# Audio.net
KiCad netlist of a schematic drawn in Altium Designer
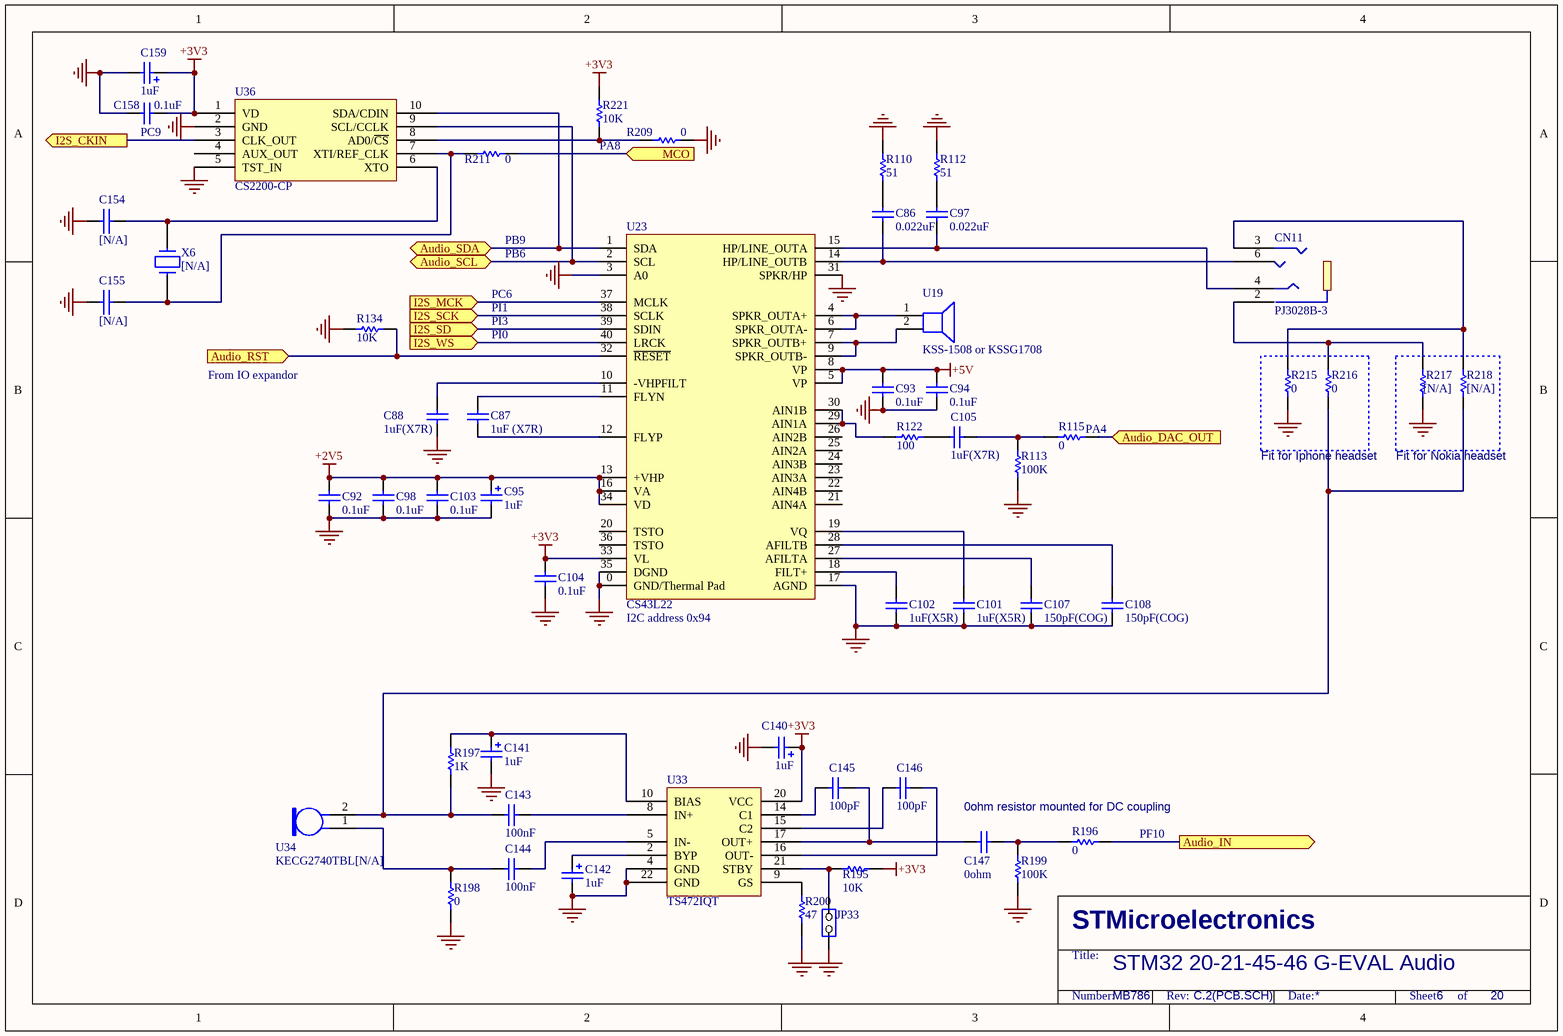
[diagram p0: Audio.SchDoc]

(export (version "E")
  (design (tool "Eeschema 10.0.6"))
  (components
    (comp (ref "C86")
      (value "0.022uF")
      (footprint "0603C")
      (description "Capacitor")
      (fields (field (name "PUBLISHER") "Altium Limited"))
      (libsource (lib "Miscellaneous Devices") (part "CAP"))
    )
    (comp (ref "C87")
      (value "1uF (X7R)")
      (footprint "0603C")
      (description "Capacitor")
      (fields (field (name "PUBLISHER") "Altium Limited"))
      (libsource (lib "Miscellaneous Devices") (part "CAP"))
    )
    (comp (ref "C88")
      (value "1uF(X7R)")
      (footprint "0603C")
      (description "Capacitor")
      (fields (field (name "PUBLISHER") "Altium Limited"))
      (libsource (lib "Miscellaneous Devices") (part "CAP"))
    )
    (comp (ref "C92")
      (value "0.1uF")
      (footprint "0402C")
      (description "Capacitor")
      (fields (field (name "PUBLISHER") "Altium Limited"))
      (libsource (lib "Miscellaneous Devices") (part "CAP"))
    )
    (comp (ref "C93")
      (value "0.1uF")
      (footprint "0402C")
      (description "Capacitor")
      (fields (field (name "PUBLISHER") "Altium Limited"))
      (libsource (lib "Miscellaneous Devices") (part "CAP"))
    )
    (comp (ref "C94")
      (value "0.1uF")
      (footprint "0402C")
      (description "Capacitor")
      (fields (field (name "PUBLISHER") "Altium Limited"))
      (libsource (lib "Miscellaneous Devices") (part "CAP"))
    )
    (comp (ref "C95")
      (value "1uF")
      (footprint "TAN-A")
      (description "Polarized Capacitor (Radial)")
      (fields (field (name "PUBLISHER") "Altium Limited"))
      (libsource (lib "Miscellaneous Devices") (part "Cap Pol1"))
    )
    (comp (ref "C97")
      (value "0.022uF")
      (footprint "0603C")
      (description "Capacitor")
      (fields (field (name "PUBLISHER") "Altium Limited"))
      (libsource (lib "Miscellaneous Devices") (part "CAP"))
    )
    (comp (ref "C98")
      (value "0.1uF")
      (footprint "0402C")
      (description "Capacitor")
      (fields (field (name "PUBLISHER") "Altium Limited"))
      (libsource (lib "Miscellaneous Devices") (part "CAP"))
    )
    (comp (ref "C101")
      (value "1uF(X5R)")
      (footprint "0603C")
      (description "Capacitor")
      (fields (field (name "PUBLISHER") "Altium Limited"))
      (libsource (lib "Miscellaneous Devices") (part "CAP"))
    )
    (comp (ref "C102")
      (value "1uF(X5R)")
      (footprint "0603C")
      (description "Capacitor")
      (fields (field (name "PUBLISHER") "Altium Limited"))
      (libsource (lib "Miscellaneous Devices") (part "CAP"))
    )
    (comp (ref "C103")
      (value "0.1uF")
      (footprint "0402C")
      (description "Capacitor")
      (fields (field (name "PUBLISHER") "Altium Limited"))
      (libsource (lib "Miscellaneous Devices") (part "CAP"))
    )
    (comp (ref "C104")
      (value "0.1uF")
      (footprint "0402C")
      (description "Capacitor")
      (fields (field (name "PUBLISHER") "Altium Limited"))
      (libsource (lib "Miscellaneous Devices") (part "CAP"))
    )
    (comp (ref "C105")
      (value "1uF(X7R)")
      (footprint "0603C")
      (description "Capacitor")
      (fields (field (name "PUBLISHER") "Altium Limited"))
      (libsource (lib "Miscellaneous Devices") (part "CAP"))
    )
    (comp (ref "C107")
      (value "150pF(COG)")
      (footprint "0603C")
      (description "Capacitor")
      (fields (field (name "PUBLISHER") "Altium Limited"))
      (libsource (lib "Miscellaneous Devices") (part "CAP"))
    )
    (comp (ref "C108")
      (value "150pF(COG)")
      (footprint "0603C")
      (description "Capacitor")
      (fields (field (name "PUBLISHER") "Altium Limited"))
      (libsource (lib "Miscellaneous Devices") (part "CAP"))
    )
    (comp (ref "C140")
      (value "1uF")
      (footprint "TAN-A")
      (description "Polarized Capacitor (Radial)")
      (fields (field (name "PUBLISHER") "Altium Limited"))
      (libsource (lib "*") (part "Cap Pol1"))
    )
    (comp (ref "C141")
      (value "1uF")
      (footprint "TAN-A")
      (description "Polarized Capacitor (Radial)")
      (fields (field (name "PUBLISHER") "Altium Limited"))
      (libsource (lib "*") (part "Cap Pol1"))
    )
    (comp (ref "C142")
      (value "1uF")
      (footprint "TAN-A")
      (description "Polarized Capacitor (Radial)")
      (fields (field (name "PUBLISHER") "Altium Limited"))
      (libsource (lib "*") (part "Cap Pol1"))
    )
    (comp (ref "C143")
      (value "100nF")
      (footprint "0402C")
      (description "Capacitor")
      (fields (field (name "PUBLISHER") "Altium Limited"))
      (libsource (lib "Miscellaneous Devices") (part "CAP"))
    )
    (comp (ref "C144")
      (value "100nF")
      (footprint "0402C")
      (description "Capacitor")
      (fields (field (name "PUBLISHER") "Altium Limited"))
      (libsource (lib "Miscellaneous Devices") (part "CAP"))
    )
    (comp (ref "C145")
      (value "100pF")
      (footprint "0402C")
      (description "Capacitor")
      (fields (field (name "PUBLISHER") "Altium Limited"))
      (libsource (lib "Miscellaneous Devices") (part "CAP"))
    )
    (comp (ref "C146")
      (value "100pF")
      (footprint "0402C")
      (description "Capacitor")
      (fields (field (name "PUBLISHER") "Altium Limited"))
      (libsource (lib "Miscellaneous Devices") (part "CAP"))
    )
    (comp (ref "C147")
      (value "0ohm")
      (footprint "0603C")
      (description "Capacitor")
      (fields (field (name "PUBLISHER") "Altium Limited"))
      (libsource (lib "Miscellaneous Devices") (part "CAP"))
    )
    (comp (ref "C154")
      (value "[N/A]")
      (footprint "0603C")
      (description "Capacitor")
      (libsource (lib "*") (part "CAP"))
    )
    (comp (ref "C155")
      (value "[N/A]")
      (footprint "0603C")
      (description "Capacitor")
      (libsource (lib "*") (part "CAP"))
    )
    (comp (ref "C158")
      (value "0.1uF")
      (footprint "0402C")
      (description "Capacitor")
      (fields (field (name "PUBLISHER") "Altium Limited"))
      (libsource (lib "Miscellaneous Devices") (part "CAP"))
    )
    (comp (ref "C159")
      (value "1uF")
      (footprint "TAN-A")
      (description "Polarized Capacitor (Radial)")
      (fields (field (name "PUBLISHER") "Altium Limited"))
      (libsource (lib "Miscellaneous Devices") (part "Cap Pol1"))
    )
    (comp (ref "CN11") (value "PJ3028B-3") (libsource (lib "MB786") (part "PJ3028B-3")))
    (comp (ref "JP33") (value "~") (footprint "SIP2") (libsource (lib "*") (part "JP2")))
    (comp (ref "R110")
      (value "51")
      (footprint "0603R")
      (description "Resistor")
      (fields (field (name "PUBLISHER") "Altium Limited"))
      (libsource (lib "Miscellaneous Devices") (part "res1"))
    )
    (comp (ref "R112")
      (value "51")
      (footprint "0603R")
      (description "Resistor")
      (fields (field (name "PUBLISHER") "Altium Limited"))
      (libsource (lib "Miscellaneous Devices") (part "res1"))
    )
    (comp (ref "R113")
      (value "100K")
      (footprint "0402R")
      (description "Resistor")
      (fields (field (name "PUBLISHER") "Altium Limited"))
      (libsource (lib "Miscellaneous Devices") (part "res1"))
    )
    (comp (ref "R115")
      (value "0")
      (footprint "0603R")
      (description "Resistor")
      (fields (field (name "PUBLISHER") "Altium Limited"))
      (libsource (lib "Miscellaneous Devices") (part "res1"))
    )
    (comp (ref "R122")
      (value "100")
      (footprint "0603R")
      (description "Resistor")
      (fields (field (name "PUBLISHER") "Altium Limited"))
      (libsource (lib "Miscellaneous Devices") (part "res1"))
    )
    (comp (ref "R134")
      (value "10K")
      (footprint "0402R")
      (description "Resistor")
      (fields (field (name "PUBLISHER") "Altium Limited"))
      (libsource (lib "Miscellaneous Devices") (part "res1"))
    )
    (comp (ref "R195")
      (value "10K")
      (footprint "0402R")
      (description "Resistor")
      (fields (field (name "PUBLISHER") "Altium Limited"))
      (libsource (lib "Miscellaneous Devices") (part "Res1"))
    )
    (comp (ref "R196")
      (value "0")
      (footprint "0603R")
      (description "Resistor")
      (fields (field (name "PUBLISHER") "Altium Limited"))
      (libsource (lib "Miscellaneous Devices") (part "Res1"))
    )
    (comp (ref "R197")
      (value "1K")
      (footprint "0603R")
      (description "Resistor")
      (fields (field (name "PUBLISHER") "Altium Limited"))
      (libsource (lib "Miscellaneous Devices") (part "Res1"))
    )
    (comp (ref "R198")
      (value "0")
      (footprint "0603R")
      (description "Resistor")
      (fields (field (name "PUBLISHER") "Altium Limited"))
      (libsource (lib "Miscellaneous Devices") (part "Res1"))
    )
    (comp (ref "R199")
      (value "100K")
      (footprint "0402R")
      (description "Resistor")
      (fields (field (name "PUBLISHER") "Altium Limited"))
      (libsource (lib "Miscellaneous Devices") (part "Res1"))
    )
    (comp (ref "R200")
      (value "47")
      (footprint "0603R")
      (description "Resistor")
      (fields (field (name "PUBLISHER") "Altium Limited"))
      (libsource (lib "Miscellaneous Devices") (part "Res1"))
    )
    (comp (ref "R209")
      (value "0")
      (footprint "0603R")
      (description "Resistor")
      (fields (field (name "PUBLISHER") "Altium Limited"))
      (libsource (lib "Miscellaneous Devices") (part "res1"))
    )
    (comp (ref "R211")
      (value "0")
      (footprint "0603R")
      (description "Resistor")
      (fields (field (name "PUBLISHER") "Altium Limited"))
      (libsource (lib "Miscellaneous Devices") (part "res1"))
    )
    (comp (ref "R215")
      (value "0")
      (footprint "0603R")
      (description "Resistor")
      (fields (field (name "PUBLISHER") "Altium Limited"))
      (libsource (lib "Miscellaneous Devices") (part "res1"))
    )
    (comp (ref "R216")
      (value "0")
      (footprint "0603R")
      (description "Resistor")
      (fields (field (name "PUBLISHER") "Altium Limited"))
      (libsource (lib "Miscellaneous Devices") (part "res1"))
    )
    (comp (ref "R217")
      (value "[N/A]")
      (footprint "0603R")
      (description "Resistor")
      (fields (field (name "PUBLISHER") "Altium Limited"))
      (libsource (lib "Miscellaneous Devices") (part "res1"))
    )
    (comp (ref "R218")
      (value "[N/A]")
      (footprint "0603R")
      (description "Resistor")
      (fields (field (name "PUBLISHER") "Altium Limited"))
      (libsource (lib "Miscellaneous Devices") (part "res1"))
    )
    (comp (ref "R221")
      (value "10K")
      (footprint "0402R")
      (description "Resistor")
      (fields (field (name "PUBLISHER") "Altium Limited"))
      (libsource (lib "Miscellaneous Devices") (part "Res1"))
    )
    (comp (ref "U19")
      (value "KSS-1508 or KSSG1708")
      (footprint "KS1708")
      (description "Loudspeaker")
      (fields (field (name "PUBLISHER") "Altium Limited"))
      (libsource (lib "Miscellaneous Devices") (part "Speaker"))
    )
    (comp (ref "U23") (value "CS43L22") (footprint "QFN40(6*6)") (libsource (lib "MB784") (part "CS43L22")))
    (comp (ref "U33") (value "TS472IQT") (footprint "QFN24(4X4)") (libsource (lib "MB786") (part "TS472IQT")))
    (comp (ref "U34")
      (value "KECG2740TBL[N/A]")
      (footprint "KEC2740")
      (description "Microphone")
      (fields (field (name "PUBLISHER") "Altium Limited"))
      (libsource (lib "Miscellaneous Devices") (part "Mic2"))
    )
    (comp (ref "U36") (value "CS2200-CP") (libsource (lib "MB786") (part "CS2200-CP")))
    (comp (ref "X6")
      (value "[N/A]")
      (footprint "XTAL_socket")
      (description "Crystal")
      (libsource (lib "*") (part "CRYSTAL"))
    )
  )
  (nets
    (net (code "1") (name "+2V5") (class "Default")
      (node (ref "C103") (pin "2") (pinfunction "2_2") (pintype "passive"))
      (node (ref "C92") (pin "2") (pinfunction "2_2") (pintype "passive"))
      (node (ref "C95") (pin "1") (pinfunction "1_1") (pintype "passive"))
      (node (ref "C98") (pin "2") (pinfunction "2_2") (pintype "passive"))
      (node (ref "U23") (pin "13") (pinfunction "+VHP_13") (pintype "passive"))
      (node (ref "U23") (pin "16") (pinfunction "VA_16") (pintype "passive"))
      (node (ref "U23") (pin "34") (pinfunction "VD_34") (pintype "passive"))
    )
    (net (code "2") (name "+3V3") (class "Default")
      (node (ref "C104") (pin "2") (pinfunction "2_2") (pintype "passive"))
      (node (ref "C140") (pin "1") (pinfunction "1_1") (pintype "passive"))
      (node (ref "C158") (pin "1") (pinfunction "1_1") (pintype "passive"))
      (node (ref "C159") (pin "1") (pinfunction "1_1") (pintype "passive"))
      (node (ref "R195") (pin "1") (pinfunction "1_1") (pintype "passive"))
      (node (ref "R221") (pin "1") (pinfunction "1_1") (pintype "passive"))
      (node (ref "U23") (pin "33") (pinfunction "VL_33") (pintype "passive"))
      (node (ref "U33") (pin "20") (pinfunction "VCC_20") (pintype "passive"))
      (node (ref "U36") (pin "1") (pinfunction "VD_1") (pintype "passive"))
    )
    (net (code "3") (name "+5V") (class "Default")
      (node (ref "C93") (pin "1") (pinfunction "1_1") (pintype "passive"))
      (node (ref "C94") (pin "1") (pinfunction "1_1") (pintype "passive"))
      (node (ref "U23") (pin "5") (pinfunction "VP_5") (pintype "passive"))
      (node (ref "U23") (pin "8") (pinfunction "VP_8") (pintype "passive"))
    )
    (net (code "4") (name "/Audio_DAC_OUT") (class "Default")
      (node (ref "R115") (pin "2") (pinfunction "2_2") (pintype "passive"))
    )
    (net (code "5") (name "/Audio_IN") (class "Default")
      (node (ref "R196") (pin "1") (pinfunction "1_1") (pintype "passive"))
    )
    (net (code "6") (name "/Audio_RST") (class "Default")
      (node (ref "R134") (pin "1") (pinfunction "1_1") (pintype "passive"))
      (node (ref "U23") (pin "32") (pinfunction "~{RESET}_32") (pintype "passive"))
    )
    (net (code "7") (name "/Audio_SCL") (class "Default")
      (node (ref "U23") (pin "2") (pinfunction "SCL_2") (pintype "passive"))
      (node (ref "U36") (pin "9") (pinfunction "SCL/CCLK_9") (pintype "passive"))
    )
    (net (code "8") (name "/Audio_SDA") (class "Default")
      (node (ref "U23") (pin "1") (pinfunction "SDA_1") (pintype "passive"))
      (node (ref "U36") (pin "10") (pinfunction "SDA/CDIN_10") (pintype "passive"))
    )
    (net (code "9") (name "/I2S_CKIN") (class "Default")
      (node (ref "U36") (pin "3") (pinfunction "CLK_OUT_3") (pintype "passive"))
    )
    (net (code "10") (name "/I2S_MCK") (class "Default")
      (node (ref "U23") (pin "37") (pinfunction "MCLK_37") (pintype "passive"))
    )
    (net (code "11") (name "/I2S_SCK") (class "Default")
      (node (ref "U23") (pin "38") (pinfunction "SCLK_38") (pintype "passive"))
    )
    (net (code "12") (name "/I2S_SD") (class "Default")
      (node (ref "U23") (pin "39") (pinfunction "SDIN_39") (pintype "passive"))
    )
    (net (code "13") (name "/I2S_WS") (class "Default")
      (node (ref "U23") (pin "40") (pinfunction "LRCK_40") (pintype "passive"))
    )
    (net (code "14") (name "/MCO") (class "Default")
      (node (ref "R211") (pin "1") (pinfunction "1_1") (pintype "passive"))
    )
    (net (code "15") (name "GND") (class "Default")
      (node (ref "C101") (pin "1") (pinfunction "1_1") (pintype "passive"))
      (node (ref "C102") (pin "1") (pinfunction "1_1") (pintype "passive"))
      (node (ref "C103") (pin "1") (pinfunction "1_1") (pintype "passive"))
      (node (ref "C104") (pin "1") (pinfunction "1_1") (pintype "passive"))
      (node (ref "C107") (pin "1") (pinfunction "1_1") (pintype "passive"))
      (node (ref "C108") (pin "1") (pinfunction "1_1") (pintype "passive"))
      (node (ref "C140") (pin "2") (pinfunction "2_2") (pintype "passive"))
      (node (ref "C141") (pin "2") (pinfunction "2_2") (pintype "passive"))
      (node (ref "C142") (pin "2") (pinfunction "2_2") (pintype "passive"))
      (node (ref "C154") (pin "2") (pinfunction "2_2") (pintype "passive"))
      (node (ref "C155") (pin "2") (pinfunction "2_2") (pintype "passive"))
      (node (ref "C158") (pin "2") (pinfunction "2_2") (pintype "passive"))
      (node (ref "C159") (pin "2") (pinfunction "2_2") (pintype "passive"))
      (node (ref "C88") (pin "2") (pinfunction "2_2") (pintype "passive"))
      (node (ref "C92") (pin "1") (pinfunction "1_1") (pintype "passive"))
      (node (ref "C93") (pin "2") (pinfunction "2_2") (pintype "passive"))
      (node (ref "C94") (pin "2") (pinfunction "2_2") (pintype "passive"))
      (node (ref "C95") (pin "2") (pinfunction "2_2") (pintype "passive"))
      (node (ref "C98") (pin "1") (pinfunction "1_1") (pintype "passive"))
      (node (ref "JP33") (pin "1") (pinfunction "COMMON_1") (pintype "passive"))
      (node (ref "R110") (pin "1") (pinfunction "1_1") (pintype "passive"))
      (node (ref "R112") (pin "1") (pinfunction "1_1") (pintype "passive"))
      (node (ref "R113") (pin "2") (pinfunction "2_2") (pintype "passive"))
      (node (ref "R134") (pin "2") (pinfunction "2_2") (pintype "passive"))
      (node (ref "R198") (pin "1") (pinfunction "1_1") (pintype "passive"))
      (node (ref "R199") (pin "1") (pinfunction "1_1") (pintype "passive"))
      (node (ref "R200") (pin "1") (pinfunction "1_1") (pintype "passive"))
      (node (ref "R209") (pin "1") (pinfunction "1_1") (pintype "passive"))
      (node (ref "R215") (pin "1") (pinfunction "1_1") (pintype "passive"))
      (node (ref "R217") (pin "1") (pinfunction "1_1") (pintype "passive"))
      (node (ref "U23") (pin "0") (pinfunction "GND/Thermal_Pad_0") (pintype "passive"))
      (node (ref "U23") (pin "17") (pinfunction "AGND_17") (pintype "passive"))
      (node (ref "U23") (pin "3") (pinfunction "A0_3") (pintype "passive"))
      (node (ref "U23") (pin "31") (pinfunction "SPKR/HP_31") (pintype "passive"))
      (node (ref "U23") (pin "35") (pinfunction "DGND_35") (pintype "passive"))
      (node (ref "U33") (pin "22") (pinfunction "GND_22") (pintype "passive"))
      (node (ref "U33") (pin "4") (pinfunction "GND_4") (pintype "passive"))
      (node (ref "U36") (pin "2") (pinfunction "GND_2") (pintype "passive"))
      (node (ref "U36") (pin "5") (pinfunction "TST_IN_5") (pintype "passive"))
    )
    (net (code "16") (name "Net-(C86-Pad1)") (class "Default")
      (node (ref "C86") (pin "1") (pinfunction "1_1") (pintype "passive"))
      (node (ref "R110") (pin "2") (pinfunction "2_2") (pintype "passive"))
    )
    (net (code "17") (name "Net-(C97-Pad1)") (class "Default")
      (node (ref "C97") (pin "1") (pinfunction "1_1") (pintype "passive"))
      (node (ref "R112") (pin "2") (pinfunction "2_2") (pintype "passive"))
    )
    (net (code "18") (name "Net-(C105-Pad1)") (class "Default")
      (node (ref "C105") (pin "1") (pinfunction "1_1") (pintype "passive"))
      (node (ref "R122") (pin "1") (pinfunction "1_1") (pintype "passive"))
    )
    (net (code "19") (name "Net-(C105-Pad2)") (class "Default")
      (node (ref "C105") (pin "2") (pinfunction "2_2") (pintype "passive"))
      (node (ref "R113") (pin "1") (pinfunction "1_1") (pintype "passive"))
      (node (ref "R115") (pin "1") (pinfunction "1_1") (pintype "passive"))
    )
    (net (code "20") (name "Net-(C143-Pad1)") (class "Default")
      (node (ref "C143") (pin "1") (pinfunction "1_1") (pintype "passive"))
      (node (ref "R197") (pin "1") (pinfunction "1_1") (pintype "passive"))
      (node (ref "R216") (pin "1") (pinfunction "1_1") (pintype "passive"))
      (node (ref "R218") (pin "1") (pinfunction "1_1") (pintype "passive"))
      (node (ref "U34") (pin "2") (pinfunction "2_2") (pintype "passive"))
    )
    (net (code "21") (name "Net-(C144-Pad1)") (class "Default")
      (node (ref "C144") (pin "1") (pinfunction "1_1") (pintype "passive"))
      (node (ref "R198") (pin "2") (pinfunction "2_2") (pintype "passive"))
      (node (ref "U34") (pin "1") (pinfunction "1_1") (pintype "passive"))
    )
    (net (code "22") (name "Net-(C147-Pad1)") (class "Default")
      (node (ref "C147") (pin "1") (pinfunction "1_1") (pintype "passive"))
      (node (ref "R196") (pin "2") (pinfunction "2_2") (pintype "passive"))
      (node (ref "R199") (pin "2") (pinfunction "2_2") (pintype "passive"))
    )
    (net (code "23") (name "Net-(CN11-Pad2)") (class "Default")
      (node (ref "CN11") (pin "2") (pintype "passive"))
      (node (ref "R216") (pin "2") (pinfunction "2_2") (pintype "passive"))
      (node (ref "R217") (pin "2") (pinfunction "2_2") (pintype "passive"))
    )
    (net (code "24") (name "Net-(CN11-Pad3)") (class "Default")
      (node (ref "CN11") (pin "3") (pintype "passive"))
      (node (ref "R215") (pin "2") (pinfunction "2_2") (pintype "passive"))
      (node (ref "R218") (pin "2") (pinfunction "2_2") (pintype "passive"))
    )
    (net (code "25") (name "Net-(JP33-NO)") (class "Default")
      (node (ref "JP33") (pin "2") (pinfunction "NO_2") (pintype "passive"))
      (node (ref "R195") (pin "2") (pinfunction "2_2") (pintype "passive"))
      (node (ref "U33") (pin "21") (pinfunction "STBY_21") (pintype "passive"))
    )
    (net (code "26") (name "Net-(U19-+)") (class "Default")
      (node (ref "U19") (pin "1") (pinfunction "+_1") (pintype "passive"))
      (node (ref "U23") (pin "4") (pinfunction "SPKR_OUTA+_4") (pintype "passive"))
      (node (ref "U23") (pin "6") (pinfunction "SPKR_OUTA-_6") (pintype "passive"))
    )
    (net (code "27") (name "Net-(U19--)") (class "Default")
      (node (ref "U19") (pin "2") (pinfunction "-_2") (pintype "passive"))
      (node (ref "U23") (pin "7") (pinfunction "SPKR_OUTB+_7") (pintype "passive"))
      (node (ref "U23") (pin "9") (pinfunction "SPKR_OUTB-_9") (pintype "passive"))
    )
    (net (code "28") (name "Net-(U23--VHPFILT)") (class "Default")
      (node (ref "C88") (pin "1") (pinfunction "1_1") (pintype "passive"))
      (node (ref "U23") (pin "10") (pinfunction "-VHPFILT_10") (pintype "passive"))
    )
    (net (code "29") (name "Net-(U23-AFILTA)") (class "Default")
      (node (ref "C107") (pin "2") (pinfunction "2_2") (pintype "passive"))
      (node (ref "U23") (pin "27") (pinfunction "AFILTA_27") (pintype "passive"))
    )
    (net (code "30") (name "Net-(U23-AFILTB)") (class "Default")
      (node (ref "C108") (pin "2") (pinfunction "2_2") (pintype "passive"))
      (node (ref "U23") (pin "28") (pinfunction "AFILTB_28") (pintype "passive"))
    )
    (net (code "31") (name "Net-(U23-AIN1A)") (class "Default")
      (node (ref "R122") (pin "2") (pinfunction "2_2") (pintype "passive"))
      (node (ref "U23") (pin "29") (pinfunction "AIN1A_29") (pintype "passive"))
      (node (ref "U23") (pin "30") (pinfunction "AIN1B_30") (pintype "passive"))
    )
    (net (code "32") (name "Net-(U23-FILT+)") (class "Default")
      (node (ref "C102") (pin "2") (pinfunction "2_2") (pintype "passive"))
      (node (ref "U23") (pin "18") (pinfunction "FILT+_18") (pintype "passive"))
    )
    (net (code "33") (name "Net-(U23-FLYN)") (class "Default")
      (node (ref "C87") (pin "2") (pinfunction "2_2") (pintype "passive"))
      (node (ref "U23") (pin "11") (pinfunction "FLYN_11") (pintype "passive"))
    )
    (net (code "34") (name "Net-(U23-FLYP)") (class "Default")
      (node (ref "C87") (pin "1") (pinfunction "1_1") (pintype "passive"))
      (node (ref "U23") (pin "12") (pinfunction "FLYP_12") (pintype "passive"))
    )
    (net (code "35") (name "Net-(U23-HP{slash}LINE_OUTA)") (class "Default")
      (node (ref "C97") (pin "2") (pinfunction "2_2") (pintype "passive"))
      (node (ref "CN11") (pin "4") (pintype "passive"))
      (node (ref "U23") (pin "15") (pinfunction "HP/LINE_OUTA_15") (pintype "passive"))
    )
    (net (code "36") (name "Net-(U23-HP{slash}LINE_OUTB)") (class "Default")
      (node (ref "C86") (pin "2") (pinfunction "2_2") (pintype "passive"))
      (node (ref "CN11") (pin "6") (pintype "passive"))
      (node (ref "U23") (pin "14") (pinfunction "HP/LINE_OUTB_14") (pintype "passive"))
    )
    (net (code "37") (name "Net-(U23-VQ)") (class "Default")
      (node (ref "C101") (pin "2") (pinfunction "2_2") (pintype "passive"))
      (node (ref "U23") (pin "19") (pinfunction "VQ_19") (pintype "passive"))
    )
    (net (code "38") (name "Net-(U33-BIAS)") (class "Default")
      (node (ref "C141") (pin "1") (pinfunction "1_1") (pintype "passive"))
      (node (ref "R197") (pin "2") (pinfunction "2_2") (pintype "passive"))
      (node (ref "U33") (pin "10") (pinfunction "BIAS_10") (pintype "passive"))
    )
    (net (code "39") (name "Net-(U33-BYP)") (class "Default")
      (node (ref "C142") (pin "1") (pinfunction "1_1") (pintype "passive"))
      (node (ref "U33") (pin "2") (pinfunction "BYP_2") (pintype "passive"))
    )
    (net (code "40") (name "Net-(U33-C1)") (class "Default")
      (node (ref "C145") (pin "2") (pinfunction "2_2") (pintype "passive"))
      (node (ref "U33") (pin "14") (pinfunction "C1_14") (pintype "passive"))
    )
    (net (code "41") (name "Net-(U33-C2)") (class "Default")
      (node (ref "C146") (pin "2") (pinfunction "2_2") (pintype "passive"))
      (node (ref "U33") (pin "15") (pinfunction "C2_15") (pintype "passive"))
    )
    (net (code "42") (name "Net-(U33-GS)") (class "Default")
      (node (ref "R200") (pin "2") (pinfunction "2_2") (pintype "passive"))
      (node (ref "U33") (pin "9") (pinfunction "GS_9") (pintype "passive"))
    )
    (net (code "43") (name "Net-(U33-IN+)") (class "Default")
      (node (ref "C143") (pin "2") (pinfunction "2_2") (pintype "passive"))
      (node (ref "U33") (pin "8") (pinfunction "IN+_8") (pintype "passive"))
    )
    (net (code "44") (name "Net-(U33-IN-)") (class "Default")
      (node (ref "C144") (pin "2") (pinfunction "2_2") (pintype "passive"))
      (node (ref "U33") (pin "5") (pinfunction "IN-_5") (pintype "passive"))
    )
    (net (code "45") (name "Net-(U33-OUT+)") (class "Default")
      (node (ref "C145") (pin "1") (pinfunction "1_1") (pintype "passive"))
      (node (ref "C147") (pin "2") (pinfunction "2_2") (pintype "passive"))
      (node (ref "U33") (pin "17") (pinfunction "OUT+_17") (pintype "passive"))
    )
    (net (code "46") (name "Net-(U33-OUT-)") (class "Default")
      (node (ref "C146") (pin "1") (pinfunction "1_1") (pintype "passive"))
      (node (ref "U33") (pin "16") (pinfunction "OUT-_16") (pintype "passive"))
    )
    (net (code "47") (name "Net-(U36-AD0{slash}~{CS})") (class "Default")
      (node (ref "R209") (pin "2") (pinfunction "2_2") (pintype "passive"))
      (node (ref "R221") (pin "2") (pinfunction "2_2") (pintype "passive"))
      (node (ref "U36") (pin "8") (pinfunction "AD0/~{CS}_8") (pintype "passive"))
    )
    (net (code "48") (name "Net-(U36-XTI{slash}REF_CLK)") (class "Default")
      (node (ref "C155") (pin "1") (pinfunction "1_1") (pintype "passive"))
      (node (ref "R211") (pin "2") (pinfunction "2_2") (pintype "passive"))
      (node (ref "U36") (pin "7") (pinfunction "XTI/REF_CLK_7") (pintype "passive"))
      (node (ref "X6") (pin "1") (pinfunction "1_1") (pintype "passive"))
    )
    (net (code "49") (name "Net-(U36-XTO)") (class "Default")
      (node (ref "C154") (pin "1") (pinfunction "1_1") (pintype "passive"))
      (node (ref "U36") (pin "6") (pinfunction "XTO_6") (pintype "passive"))
      (node (ref "X6") (pin "2") (pinfunction "2_2") (pintype "passive"))
    )
    (net (code "50") (name "unconnected-(U23-AIN2A-Pad25)") (class "Default")
      (node (ref "U23") (pin "25") (pinfunction "AIN2A_25") (pintype "passive"))
    )
    (net (code "51") (name "unconnected-(U23-AIN2B-Pad26)") (class "Default")
      (node (ref "U23") (pin "26") (pinfunction "AIN2B_26") (pintype "passive"))
    )
    (net (code "52") (name "unconnected-(U23-AIN3A-Pad23)") (class "Default")
      (node (ref "U23") (pin "23") (pinfunction "AIN3A_23") (pintype "passive"))
    )
    (net (code "53") (name "unconnected-(U23-AIN3B-Pad24)") (class "Default")
      (node (ref "U23") (pin "24") (pinfunction "AIN3B_24") (pintype "passive"))
    )
    (net (code "54") (name "unconnected-(U23-AIN4A-Pad21)") (class "Default")
      (node (ref "U23") (pin "21") (pinfunction "AIN4A_21") (pintype "passive"))
    )
    (net (code "55") (name "unconnected-(U23-AIN4B-Pad22)") (class "Default")
      (node (ref "U23") (pin "22") (pinfunction "AIN4B_22") (pintype "passive"))
    )
    (net (code "56") (name "unconnected-(U23-TSTO-Pad20)") (class "Default")
      (node (ref "U23") (pin "20") (pinfunction "TSTO_20") (pintype "passive"))
    )
    (net (code "57") (name "unconnected-(U23-TSTO-Pad36)") (class "Default")
      (node (ref "U23") (pin "36") (pinfunction "TSTO_36") (pintype "passive"))
    )
    (net (code "58") (name "unconnected-(U36-AUX_OUT-Pad4)") (class "Default")
      (node (ref "U36") (pin "4") (pinfunction "AUX_OUT_4") (pintype "passive"))
    )
  )
)
